# ui-jetson-nano.net
KiCad netlist of a schematic drawn in Altium Designer
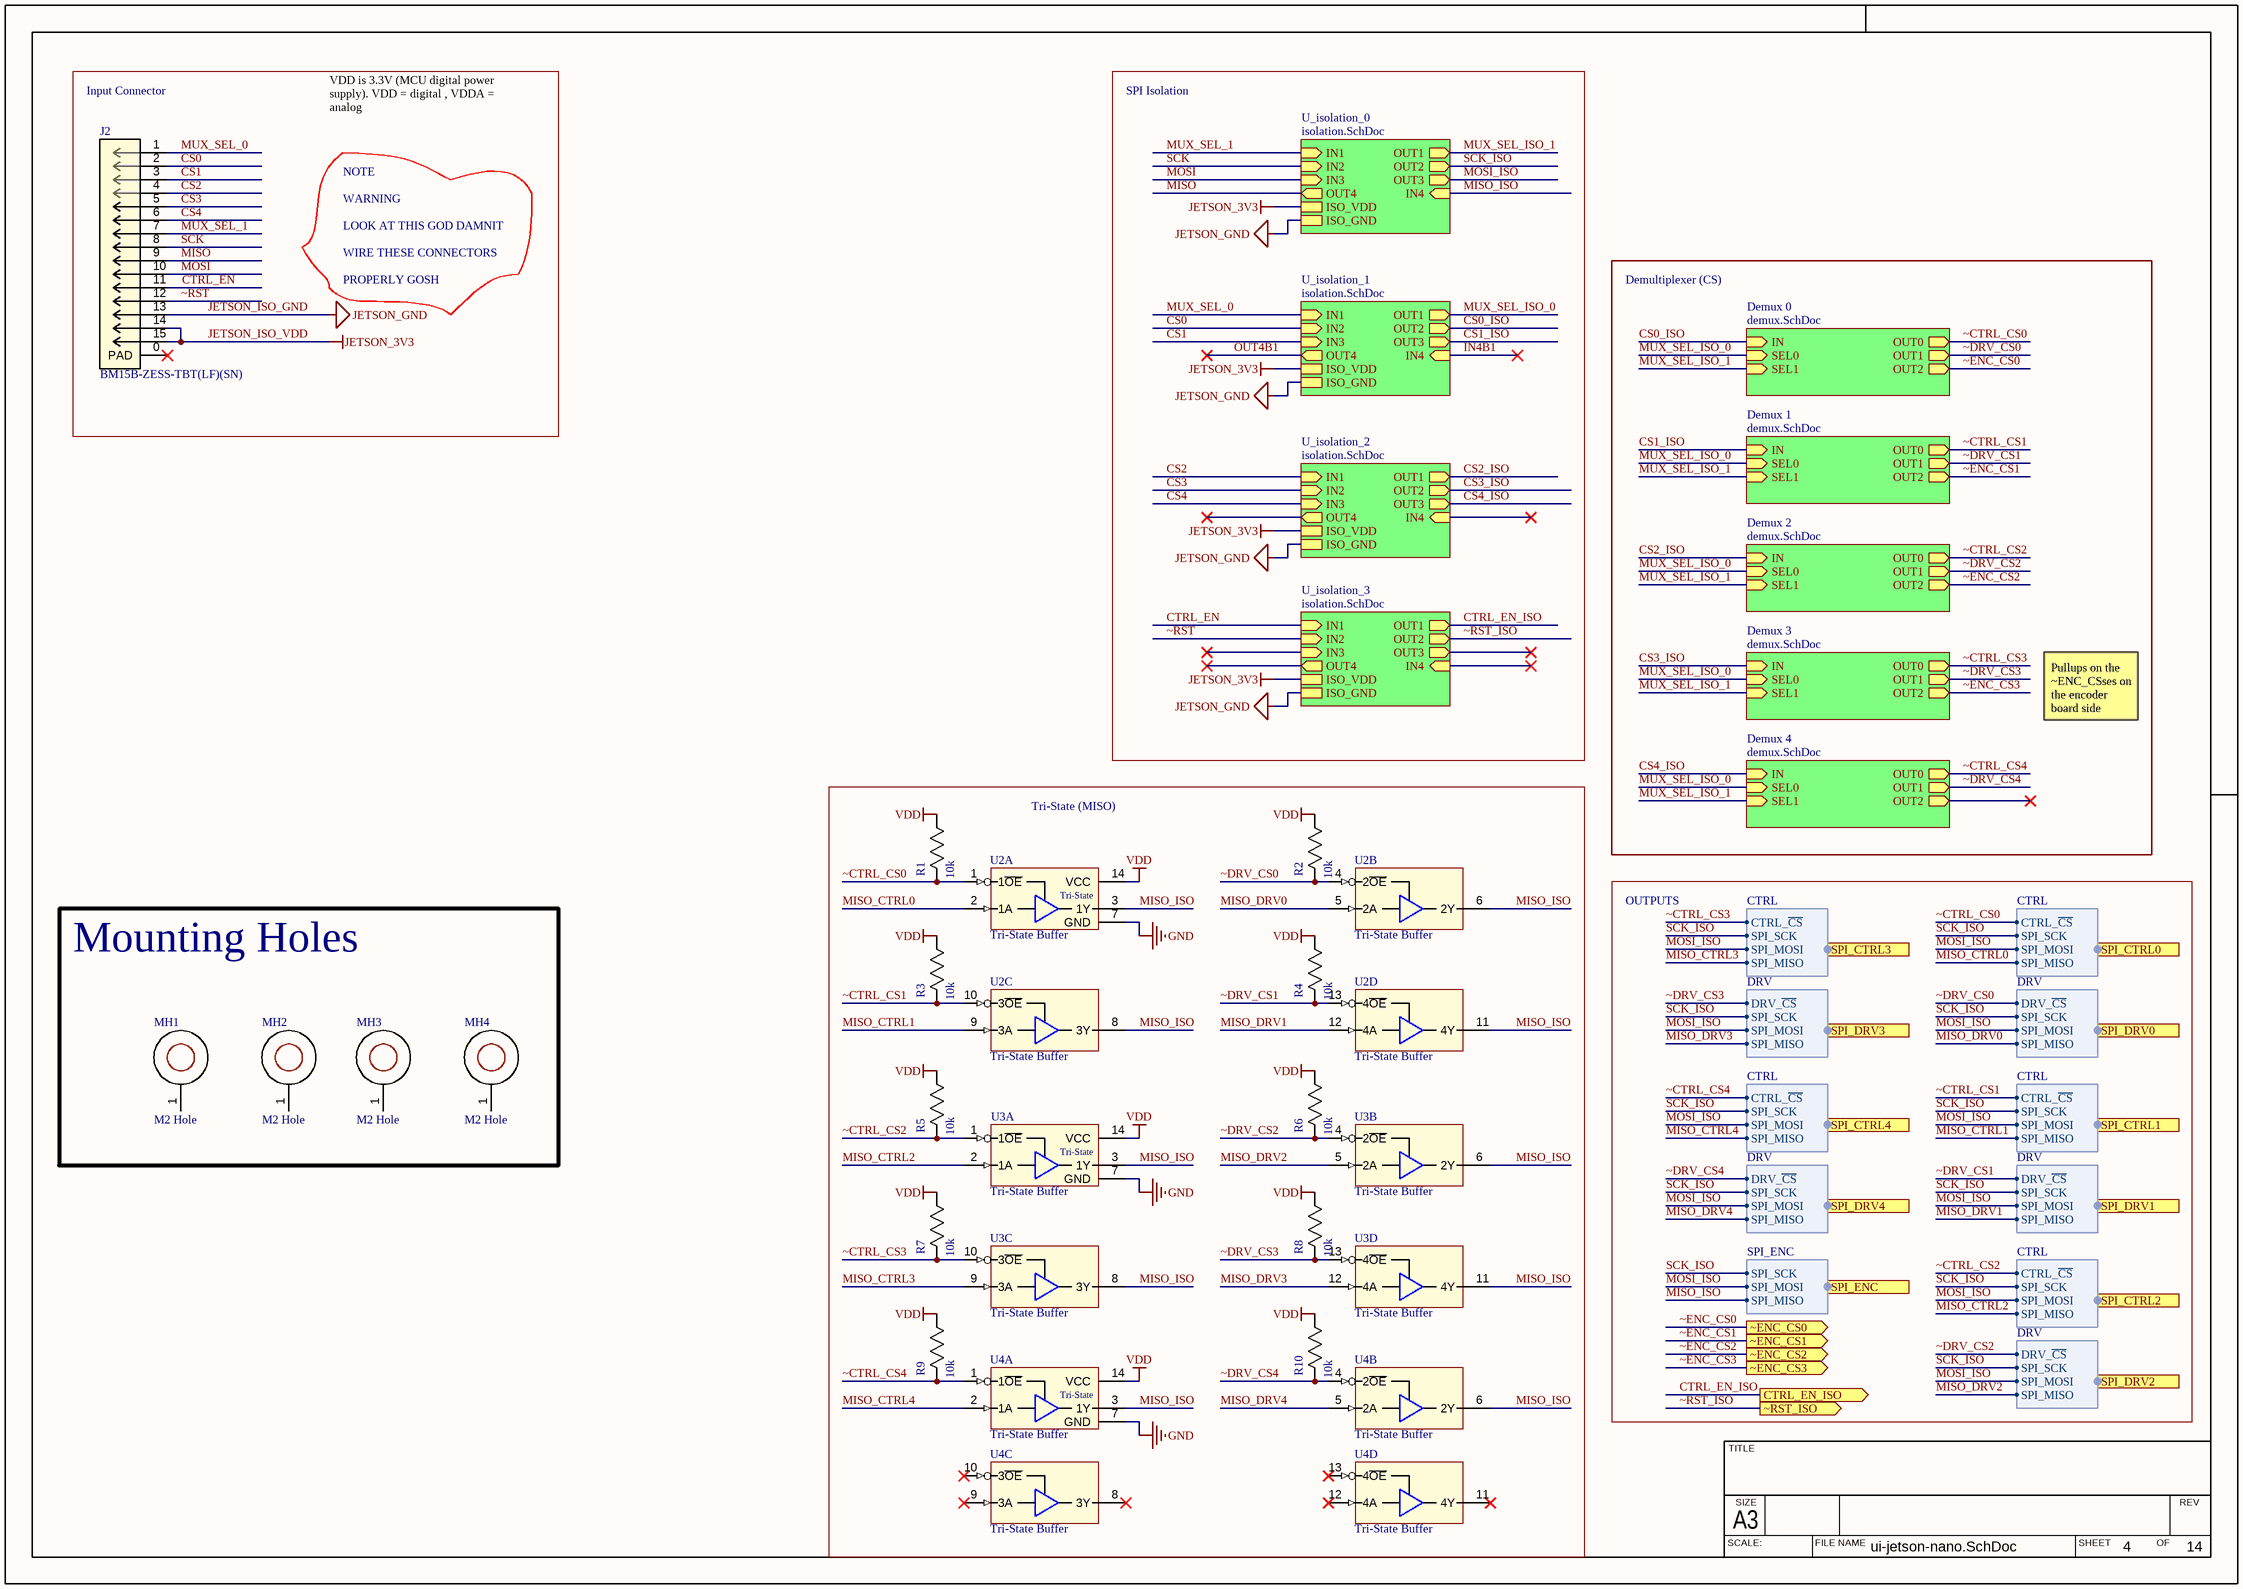
[diagram p0: ui-jetson-nano.SchDoc]

(export (version "E")
  (design (tool "Eeschema 10.0.6"))
  (components
    (comp (ref "J2")
      (value "BM15B-ZESS-TBT(LF)(SN)")
      (footprint "JST ZE SMT 15POS")
      (description "CONN HEADER VERT SMD 15POS ZE")
      (fields (field (name "PART NUMBER") "CN 15POS JST ZE SMT"))
      (libsource (lib "Connector_Library") (part "CN 15POS JST ZE SMT"))
    )
    (comp (ref "MH1")
      (value "M2 Hole")
      (footprint "Mounting Hole M2")
      (description "Standard M2 Mounting Hole for M2 Standoff")
      (fields (field (name "PART NUMBER") "MOUNTING HOLE M2"))
      (libsource (lib "IC_Library") (part "MOUNTING HOLE M2"))
    )
    (comp (ref "MH2")
      (value "M2 Hole")
      (footprint "Mounting Hole M2")
      (description "Standard M2 Mounting Hole for M2 Standoff")
      (fields (field (name "PART NUMBER") "MOUNTING HOLE M2"))
      (libsource (lib "IC_Library") (part "MOUNTING HOLE M2"))
    )
    (comp (ref "MH3")
      (value "M2 Hole")
      (footprint "Mounting Hole M2")
      (description "Standard M2 Mounting Hole for M2 Standoff")
      (fields (field (name "PART NUMBER") "MOUNTING HOLE M2"))
      (libsource (lib "IC_Library") (part "MOUNTING HOLE M2"))
    )
    (comp (ref "MH4")
      (value "M2 Hole")
      (footprint "Mounting Hole M2")
      (description "Standard M2 Mounting Hole for M2 Standoff")
      (fields (field (name "PART NUMBER") "MOUNTING HOLE M2"))
      (libsource (lib "IC_Library") (part "MOUNTING HOLE M2"))
    )
    (comp (ref "R1")
      (value "10k")
      (footprint "0603")
      (description "RES SMD 10K OHM 1% 1/8W 0805")
      (fields (field (name "TOLERANCE") "5%") (field (name "PART NUMBER") "RES 10k 1/8W 1%"))
      (libsource (lib "Resistor_Library") (part "RES_DEFAULT"))
    )
    (comp (ref "R2")
      (value "10k")
      (footprint "0603")
      (description "RES SMD 10K OHM 1% 1/8W 0805")
      (fields (field (name "TOLERANCE") "5%") (field (name "PART NUMBER") "RES 10k 1/8W 1%"))
      (libsource (lib "Resistor_Library") (part "RES_DEFAULT"))
    )
    (comp (ref "R3")
      (value "10k")
      (footprint "0603")
      (description "RES SMD 10K OHM 1% 1/8W 0805")
      (fields (field (name "TOLERANCE") "5%") (field (name "PART NUMBER") "RES 10k 1/8W 1%"))
      (libsource (lib "Resistor_Library") (part "RES_DEFAULT"))
    )
    (comp (ref "R4")
      (value "10k")
      (footprint "0603")
      (description "RES SMD 10K OHM 1% 1/8W 0805")
      (fields (field (name "TOLERANCE") "5%") (field (name "PART NUMBER") "RES 10k 1/8W 1%"))
      (libsource (lib "Resistor_Library") (part "RES_DEFAULT"))
    )
    (comp (ref "R5")
      (value "10k")
      (footprint "0603")
      (description "RES SMD 10K OHM 1% 1/8W 0805")
      (fields (field (name "TOLERANCE") "5%") (field (name "PART NUMBER") "RES 10k 1/8W 1%"))
      (libsource (lib "Resistor_Library") (part "RES_DEFAULT"))
    )
    (comp (ref "R6")
      (value "10k")
      (footprint "0603")
      (description "RES SMD 10K OHM 1% 1/8W 0805")
      (fields (field (name "TOLERANCE") "5%") (field (name "PART NUMBER") "RES 10k 1/8W 1%"))
      (libsource (lib "Resistor_Library") (part "RES_DEFAULT"))
    )
    (comp (ref "R7")
      (value "10k")
      (footprint "0603")
      (description "RES SMD 10K OHM 1% 1/8W 0805")
      (fields (field (name "TOLERANCE") "5%") (field (name "PART NUMBER") "RES 10k 1/8W 1%"))
      (libsource (lib "Resistor_Library") (part "RES_DEFAULT"))
    )
    (comp (ref "R8")
      (value "10k")
      (footprint "0603")
      (description "RES SMD 10K OHM 1% 1/8W 0805")
      (fields (field (name "TOLERANCE") "5%") (field (name "PART NUMBER") "RES 10k 1/8W 1%"))
      (libsource (lib "Resistor_Library") (part "RES_DEFAULT"))
    )
    (comp (ref "R9")
      (value "10k")
      (footprint "0603")
      (description "RES SMD 10K OHM 1% 1/8W 0805")
      (fields (field (name "TOLERANCE") "5%") (field (name "PART NUMBER") "RES 10k 1/8W 1%"))
      (libsource (lib "Resistor_Library") (part "RES_DEFAULT"))
    )
    (comp (ref "R10")
      (value "10k")
      (footprint "0603")
      (description "RES SMD 10K OHM 1% 1/8W 0805")
      (fields (field (name "TOLERANCE") "5%") (field (name "PART NUMBER") "RES 10k 1/8W 1%"))
      (libsource (lib "Resistor_Library") (part "RES_DEFAULT"))
    )
    (comp (ref "U2")
      (value "Tri-State Buffer")
      (footprint "14-TSSOP")
      (description "Buffer, Non-Inverting 4 Element 1 Bit per Element 3-State Output 14-TSSOP")
      (fields (field (name "PART NUMBER") "SN74LVC125APWR"))
      (libsource (lib "IC_Library") (part "SN74LVC125APWR"))
    )
    (comp (ref "U3")
      (value "Tri-State Buffer")
      (footprint "14-TSSOP")
      (description "Buffer, Non-Inverting 4 Element 1 Bit per Element 3-State Output 14-TSSOP")
      (fields (field (name "PART NUMBER") "SN74LVC125APWR"))
      (libsource (lib "IC_Library") (part "SN74LVC125APWR"))
    )
    (comp (ref "U4")
      (value "Tri-State Buffer")
      (footprint "14-TSSOP")
      (description "Buffer, Non-Inverting 4 Element 1 Bit per Element 3-State Output 14-TSSOP")
      (fields (field (name "PART NUMBER") "SN74LVC125APWR"))
      (libsource (lib "IC_Library") (part "SN74LVC125APWR"))
    )
  )
  (nets
    (net (code "4") (name "/CS0") (class "Default")
      (node (ref "J2") (pin "2") (pinfunction "2_2") (pintype "passive"))
    )
    (net (code "6") (name "/CS1") (class "Default")
      (node (ref "J2") (pin "3") (pinfunction "3_3") (pintype "passive"))
    )
    (net (code "8") (name "/CS2") (class "Default")
      (node (ref "J2") (pin "4") (pinfunction "4_4") (pintype "passive"))
    )
    (net (code "10") (name "/CS3") (class "Default")
      (node (ref "J2") (pin "5") (pinfunction "5_5") (pintype "passive"))
    )
    (net (code "12") (name "/CS4") (class "Default")
      (node (ref "J2") (pin "6") (pinfunction "6_6") (pintype "passive"))
    )
    (net (code "14") (name "/CTRL_EN") (class "Default")
      (node (ref "J2") (pin "11") (pinfunction "11_11") (pintype "passive"))
    )
    (net (code "20") (name "/MISO") (class "Default")
      (node (ref "J2") (pin "9") (pinfunction "9_9") (pintype "passive"))
    )
    (net (code "21") (name "/MISO_CTRL0") (class "Default")
      (node (ref "U2") (pin "2") (pinfunction "1A_2") (pintype "input"))
    )
    (net (code "22") (name "/MISO_CTRL1") (class "Default")
      (node (ref "U2") (pin "9") (pinfunction "3A_9") (pintype "input"))
    )
    (net (code "23") (name "/MISO_CTRL2") (class "Default")
      (node (ref "U3") (pin "2") (pinfunction "1A_2") (pintype "input"))
    )
    (net (code "24") (name "/MISO_CTRL3") (class "Default")
      (node (ref "U3") (pin "9") (pinfunction "3A_9") (pintype "input"))
    )
    (net (code "25") (name "/MISO_CTRL4") (class "Default")
      (node (ref "U4") (pin "2") (pinfunction "1A_2") (pintype "input"))
    )
    (net (code "26") (name "/MISO_DRV0") (class "Default")
      (node (ref "U2") (pin "5") (pinfunction "2A_5") (pintype "input"))
    )
    (net (code "27") (name "/MISO_DRV1") (class "Default")
      (node (ref "U2") (pin "12") (pinfunction "4A_12") (pintype "input"))
    )
    (net (code "28") (name "/MISO_DRV2") (class "Default")
      (node (ref "U3") (pin "5") (pinfunction "2A_5") (pintype "input"))
    )
    (net (code "29") (name "/MISO_DRV3") (class "Default")
      (node (ref "U3") (pin "12") (pinfunction "4A_12") (pintype "input"))
    )
    (net (code "30") (name "/MISO_DRV4") (class "Default")
      (node (ref "U4") (pin "5") (pinfunction "2A_5") (pintype "input"))
    )
    (net (code "31") (name "/MISO_ISO") (class "Default")
      (node (ref "U2") (pin "11") (pinfunction "4Y_11") (pintype "passive"))
      (node (ref "U2") (pin "3") (pinfunction "1Y_3") (pintype "passive"))
      (node (ref "U2") (pin "6") (pinfunction "2Y_6") (pintype "passive"))
      (node (ref "U2") (pin "8") (pinfunction "3Y_8") (pintype "passive"))
      (node (ref "U3") (pin "11") (pinfunction "4Y_11") (pintype "passive"))
      (node (ref "U3") (pin "3") (pinfunction "1Y_3") (pintype "passive"))
      (node (ref "U3") (pin "6") (pinfunction "2Y_6") (pintype "passive"))
      (node (ref "U3") (pin "8") (pinfunction "3Y_8") (pintype "passive"))
      (node (ref "U4") (pin "3") (pinfunction "1Y_3") (pintype "passive"))
      (node (ref "U4") (pin "6") (pinfunction "2Y_6") (pintype "passive"))
    )
    (net (code "32") (name "/MOSI") (class "Default")
      (node (ref "J2") (pin "10") (pinfunction "10_10") (pintype "passive"))
    )
    (net (code "34") (name "/MUX_SEL_0") (class "Default")
      (node (ref "J2") (pin "1") (pinfunction "1_1") (pintype "passive"))
    )
    (net (code "35") (name "/MUX_SEL_1") (class "Default")
      (node (ref "J2") (pin "7") (pinfunction "7_7") (pintype "passive"))
    )
    (net (code "43") (name "/SCK") (class "Default")
      (node (ref "J2") (pin "8") (pinfunction "8_8") (pintype "passive"))
    )
    (net (code "48") (name "/~CTRL_CS0") (class "Default")
      (node (ref "R1") (pin "2") (pinfunction "R2_2") (pintype "passive"))
      (node (ref "U2") (pin "1") (pinfunction "1~{OE}_1") (pintype "input"))
    )
    (net (code "49") (name "/~CTRL_CS1") (class "Default")
      (node (ref "R3") (pin "2") (pinfunction "R2_2") (pintype "passive"))
      (node (ref "U2") (pin "10") (pinfunction "3~{OE}_10") (pintype "input"))
    )
    (net (code "50") (name "/~CTRL_CS2") (class "Default")
      (node (ref "R5") (pin "2") (pinfunction "R2_2") (pintype "passive"))
      (node (ref "U3") (pin "1") (pinfunction "1~{OE}_1") (pintype "input"))
    )
    (net (code "51") (name "/~CTRL_CS3") (class "Default")
      (node (ref "R7") (pin "2") (pinfunction "R2_2") (pintype "passive"))
      (node (ref "U3") (pin "10") (pinfunction "3~{OE}_10") (pintype "input"))
    )
    (net (code "52") (name "/~CTRL_CS4") (class "Default")
      (node (ref "R9") (pin "2") (pinfunction "R2_2") (pintype "passive"))
      (node (ref "U4") (pin "1") (pinfunction "1~{OE}_1") (pintype "input"))
    )
    (net (code "53") (name "/~DRV_CS0") (class "Default")
      (node (ref "R2") (pin "2") (pinfunction "R2_2") (pintype "passive"))
      (node (ref "U2") (pin "4") (pinfunction "2~{OE}_4") (pintype "input"))
    )
    (net (code "54") (name "/~DRV_CS1") (class "Default")
      (node (ref "R4") (pin "2") (pinfunction "R2_2") (pintype "passive"))
      (node (ref "U2") (pin "13") (pinfunction "4~{OE}_13") (pintype "input"))
    )
    (net (code "55") (name "/~DRV_CS2") (class "Default")
      (node (ref "R6") (pin "2") (pinfunction "R2_2") (pintype "passive"))
      (node (ref "U3") (pin "4") (pinfunction "2~{OE}_4") (pintype "input"))
    )
    (net (code "56") (name "/~DRV_CS3") (class "Default")
      (node (ref "R8") (pin "2") (pinfunction "R2_2") (pintype "passive"))
      (node (ref "U3") (pin "13") (pinfunction "4~{OE}_13") (pintype "input"))
    )
    (net (code "57") (name "/~DRV_CS4") (class "Default")
      (node (ref "R10") (pin "2") (pinfunction "R2_2") (pintype "passive"))
      (node (ref "U4") (pin "4") (pinfunction "2~{OE}_4") (pintype "input"))
    )
    (net (code "62") (name "/~RST") (class "Default")
      (node (ref "J2") (pin "12") (pinfunction "12_12") (pintype "passive"))
    )
    (net (code "64") (name "GND") (class "Default")
      (node (ref "U2") (pin "7") (pinfunction "GND_7") (pintype "passive"))
      (node (ref "U3") (pin "7") (pinfunction "GND_7") (pintype "passive"))
      (node (ref "U4") (pin "7") (pinfunction "GND_7") (pintype "passive"))
    )
    (net (code "65") (name "JETSON_3V3") (class "Default")
      (node (ref "J2") (pin "14") (pinfunction "14_14") (pintype "passive"))
      (node (ref "J2") (pin "15") (pinfunction "15_15") (pintype "passive"))
    )
    (net (code "66") (name "JETSON_GND") (class "Default")
      (node (ref "J2") (pin "13") (pinfunction "13_13") (pintype "passive"))
    )
    (net (code "67") (name "VDD") (class "Default")
      (node (ref "R1") (pin "1") (pinfunction "R1_1") (pintype "passive"))
      (node (ref "R10") (pin "1") (pinfunction "R1_1") (pintype "passive"))
      (node (ref "R2") (pin "1") (pinfunction "R1_1") (pintype "passive"))
      (node (ref "R3") (pin "1") (pinfunction "R1_1") (pintype "passive"))
      (node (ref "R4") (pin "1") (pinfunction "R1_1") (pintype "passive"))
      (node (ref "R5") (pin "1") (pinfunction "R1_1") (pintype "passive"))
      (node (ref "R6") (pin "1") (pinfunction "R1_1") (pintype "passive"))
      (node (ref "R7") (pin "1") (pinfunction "R1_1") (pintype "passive"))
      (node (ref "R8") (pin "1") (pinfunction "R1_1") (pintype "passive"))
      (node (ref "R9") (pin "1") (pinfunction "R1_1") (pintype "passive"))
      (node (ref "U2") (pin "14") (pinfunction "VCC_14") (pintype "passive"))
      (node (ref "U3") (pin "14") (pinfunction "VCC_14") (pintype "passive"))
      (node (ref "U4") (pin "14") (pinfunction "VCC_14") (pintype "passive"))
    )
    (net (code "68") (name "unconnected-(J2-PAD-Pad0)") (class "Default")
      (node (ref "J2") (pin "0") (pinfunction "PAD_0") (pintype "passive+no_connect"))
    )
    (net (code "69") (name "unconnected-(MH1-Pad1)") (class "Default")
      (node (ref "MH1") (pin "1") (pinfunction "1_1") (pintype "passive"))
    )
    (net (code "70") (name "unconnected-(MH2-Pad1)") (class "Default")
      (node (ref "MH2") (pin "1") (pinfunction "1_1") (pintype "passive"))
    )
    (net (code "71") (name "unconnected-(MH3-Pad1)") (class "Default")
      (node (ref "MH3") (pin "1") (pinfunction "1_1") (pintype "passive"))
    )
    (net (code "72") (name "unconnected-(MH4-Pad1)") (class "Default")
      (node (ref "MH4") (pin "1") (pinfunction "1_1") (pintype "passive"))
    )
    (net (code "73") (name "unconnected-(U4C-3A-Pad9)") (class "Default")
      (node (ref "U4") (pin "9") (pinfunction "3A_9") (pintype "input+no_connect"))
    )
    (net (code "74") (name "unconnected-(U4C-3Y-Pad8)") (class "Default")
      (node (ref "U4") (pin "8") (pinfunction "3Y_8") (pintype "passive+no_connect"))
    )
    (net (code "75") (name "unconnected-(U4C-3~{OE}-Pad10)") (class "Default")
      (node (ref "U4") (pin "10") (pinfunction "3~{OE}_10") (pintype "input+no_connect"))
    )
    (net (code "76") (name "unconnected-(U4D-4A-Pad12)") (class "Default")
      (node (ref "U4") (pin "12") (pinfunction "4A_12") (pintype "input+no_connect"))
    )
    (net (code "77") (name "unconnected-(U4D-4Y-Pad11)") (class "Default")
      (node (ref "U4") (pin "11") (pinfunction "4Y_11") (pintype "passive+no_connect"))
    )
    (net (code "78") (name "unconnected-(U4D-4~{OE}-Pad13)") (class "Default")
      (node (ref "U4") (pin "13") (pinfunction "4~{OE}_13") (pintype "input+no_connect"))
    )
  )
)
